# LDR_Module_v2_SCH.net
KiCad netlist of a schematic drawn in Altium Designer
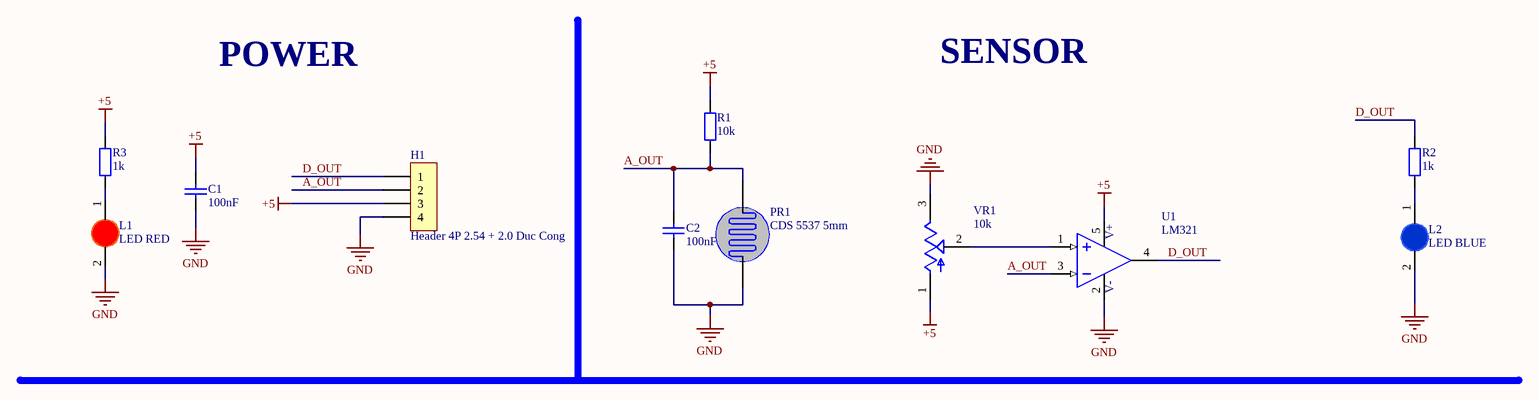
[diagram p0: LDR_Module_v2_SCH.SchDoc]

(export (version "E")
  (design (tool "Eeschema 10.0.6"))
  (components
    (comp (ref "C1")
      (value "100nF")
      (footprint "tu 0603")
      (description "Dán")
      (libsource (lib "namnt_Lib") (part "Tu 0603 104 50V 10%"))
    )
    (comp (ref "C2")
      (value "100nF")
      (footprint "tu 0603")
      (description "Dán")
      (libsource (lib "namnt_Lib") (part "Tu 0603 104 50V 10%"))
    )
    (comp (ref "H1")
      (value "Header 4P 2.54 + 2.0 Duc Cong")
      (footprint "Header 4P DC 2.54 + 2.0")
      (description "Cắm")
      (libsource (lib "namnt_Lib") (part "Header 4P 2.54 + 2.0 Duc Cong"))
    )
    (comp (ref "L1")
      (value "LED RED")
      (footprint "LED-0805-Red")
      (description "Dán")
      (libsource (lib "namnt_Lib") (part "LED 0805 Do"))
    )
    (comp (ref "L2")
      (value "LED BLUE")
      (footprint "LED-0805-Blue")
      (description "Dán")
      (libsource (lib "namnt_Lib") (part "LED 0805 Xanh Duong"))
    )
    (comp (ref "PR1")
      (value "CDS 5537 5mm")
      (footprint "Quang Tro")
      (description "Photoresistor")
      (fields (field (name "CREATOR") "Bien Nguyen"))
      (libsource (lib "namnt_Lib") (part "Quang Tro"))
    )
    (comp (ref "R1")
      (value "10k")
      (footprint "tro smd 0603")
      (description "Dán")
      (libsource (lib "namnt_Lib") (part "Tro 0603 1% 10k"))
    )
    (comp (ref "R2")
      (value "1k")
      (footprint "tro smd 0603")
      (description "Dán")
      (libsource (lib "namnt_Lib") (part "Tro 0603 1% 1k"))
    )
    (comp (ref "R3")
      (value "1k")
      (footprint "tro smd 0603")
      (description "Dán")
      (libsource (lib "namnt_Lib") (part "Tro 0603 1% 1k"))
    )
    (comp (ref "U1")
      (value "LM321")
      (footprint "xlib:sot23-5")
      (description "Opamp")
      (libsource (lib "XLib") (part "LM321"))
    )
    (comp (ref "VR1")
      (value "10k")
      (footprint "TRIM_3362P-1-102")
      (description "TRIMMER - 1/4in SQ ST CERMET ¦ Bourns 3362P-1-102")
      (fields (field (name "MF") "Bourns") (field (name "MP") "3362P-1-102"))
      (libsource (lib "namnt_Lib") (part "Bien tro vuong"))
    )
  )
  (nets
    (net (code "1") (name "+5") (class "Default")
      (node (ref "C1") (pin "1") (pinfunction "1_1") (pintype "passive"))
      (node (ref "H1") (pin "3") (pinfunction "3_3") (pintype "passive"))
      (node (ref "R1") (pin "2") (pinfunction "2_2") (pintype "passive"))
      (node (ref "R3") (pin "2") (pinfunction "2_2") (pintype "passive"))
      (node (ref "U1") (pin "5") (pinfunction "V+_5") (pintype "power_in"))
      (node (ref "VR1") (pin "1") (pinfunction "CCW_1") (pintype "passive"))
    )
    (net (code "2") (name "/A_OUT") (class "Default")
      (node (ref "C2") (pin "1") (pinfunction "1_1") (pintype "passive"))
      (node (ref "H1") (pin "2") (pinfunction "2_2") (pintype "passive"))
      (node (ref "PR1") (pin "2") (pinfunction "2_2") (pintype "passive"))
      (node (ref "R1") (pin "1") (pinfunction "1_1") (pintype "passive"))
      (node (ref "U1") (pin "3") (pinfunction "IN-_3") (pintype "input"))
    )
    (net (code "3") (name "/D_OUT") (class "Default")
      (node (ref "H1") (pin "1") (pinfunction "1_1") (pintype "passive"))
      (node (ref "R2") (pin "2") (pinfunction "2_2") (pintype "passive"))
      (node (ref "U1") (pin "4") (pinfunction "-V_4") (pintype "passive"))
    )
    (net (code "4") (name "GND") (class "Default")
      (node (ref "C1") (pin "2") (pinfunction "2_2") (pintype "passive"))
      (node (ref "C2") (pin "2") (pinfunction "2_2") (pintype "passive"))
      (node (ref "H1") (pin "4") (pinfunction "4_4") (pintype "passive"))
      (node (ref "L1") (pin "2") (pinfunction "K_2") (pintype "passive"))
      (node (ref "L2") (pin "2") (pinfunction "K_2") (pintype "passive"))
      (node (ref "PR1") (pin "1") (pinfunction "1_1") (pintype "passive"))
      (node (ref "U1") (pin "2") (pinfunction "V-_2") (pintype "power_in"))
      (node (ref "VR1") (pin "3") (pinfunction "CW_3") (pintype "passive"))
    )
    (net (code "5") (name "Net-(L1-A)") (class "Default")
      (node (ref "L1") (pin "1") (pinfunction "A_1") (pintype "passive"))
      (node (ref "R3") (pin "1") (pinfunction "1_1") (pintype "passive"))
    )
    (net (code "6") (name "Net-(L2-A)") (class "Default")
      (node (ref "L2") (pin "1") (pinfunction "A_1") (pintype "passive"))
      (node (ref "R2") (pin "1") (pinfunction "1_1") (pintype "passive"))
    )
    (net (code "7") (name "Net-(U1-IN+)") (class "Default")
      (node (ref "U1") (pin "1") (pinfunction "IN+_1") (pintype "input"))
      (node (ref "VR1") (pin "2") (pinfunction "WIPER_2") (pintype "passive"))
    )
  )
)
